# temperature_measurement.net
KiCad netlist of a schematic drawn in Altium Designer
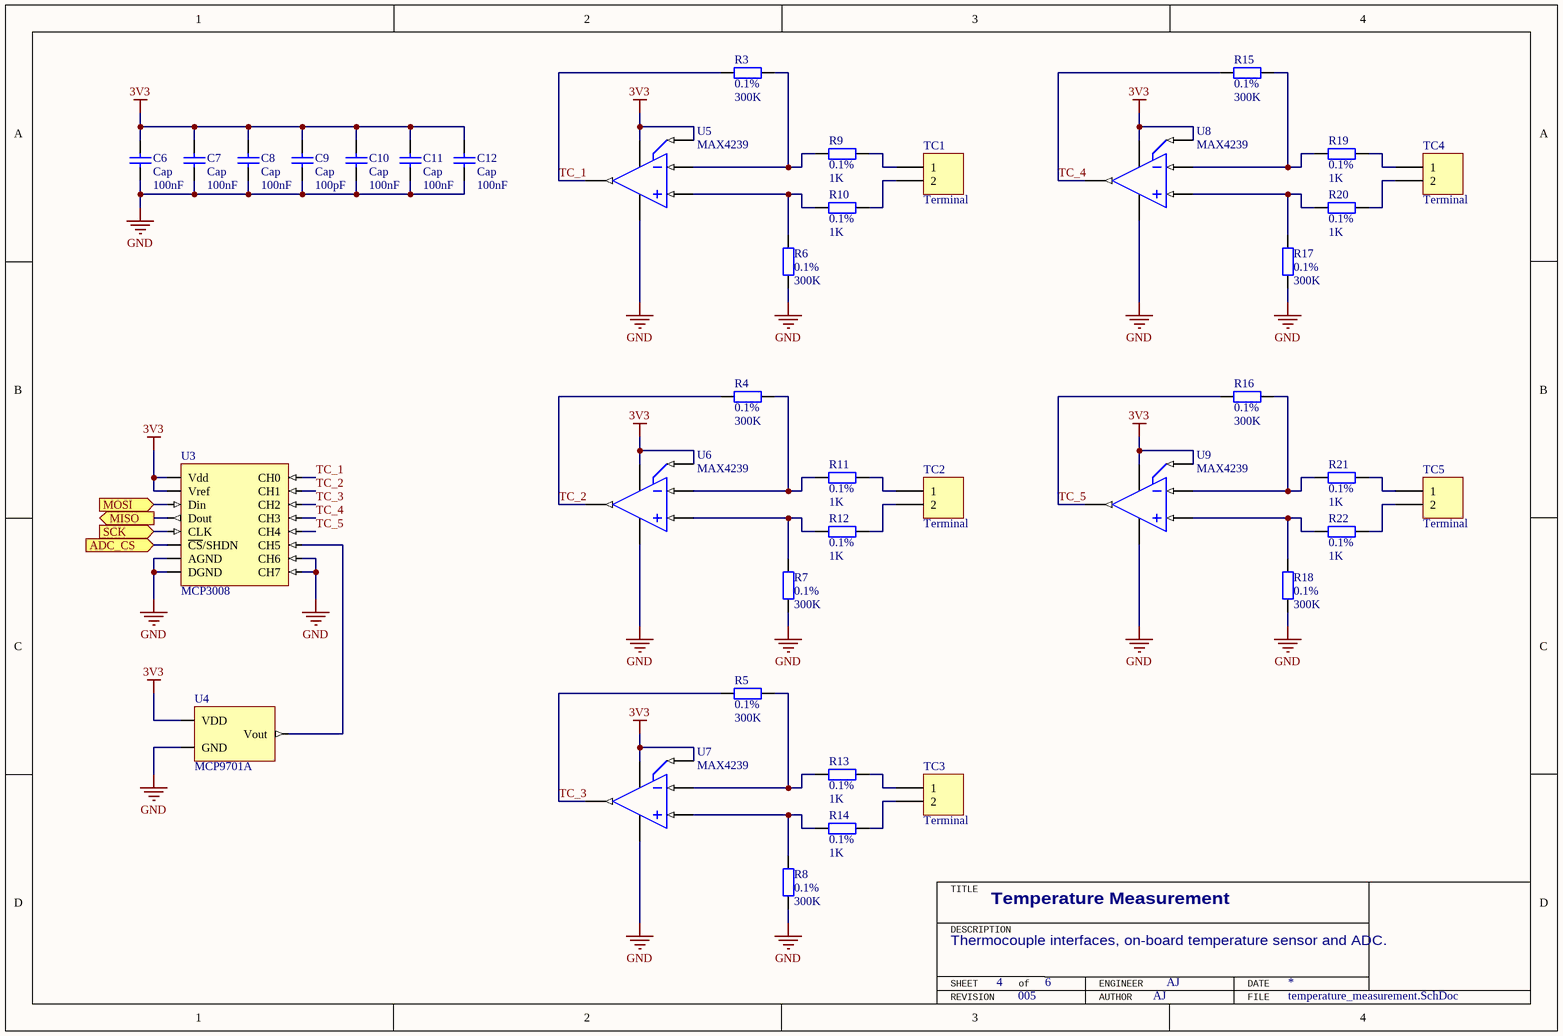
[diagram p0: temperature_measurement.SchDoc]

(export (version "E")
  (design (tool "Eeschema 10.0.6"))
  (components
    (comp (ref "C6")
      (value "Cap")
      (footprint "0603")
      (description "Capacitor")
      (fields (field (name "ALTIUM_VALUE") "100nF") (field (name "PUBLISHER") "Altium Limited"))
      (libsource (lib "Miscellaneous Devices") (part "Cap"))
    )
    (comp (ref "C7")
      (value "Cap")
      (footprint "0603")
      (description "Capacitor")
      (fields (field (name "ALTIUM_VALUE") "100nF") (field (name "PUBLISHER") "Altium Limited"))
      (libsource (lib "Miscellaneous Devices") (part "Cap"))
    )
    (comp (ref "C8")
      (value "Cap")
      (footprint "0603")
      (description "Capacitor")
      (fields (field (name "ALTIUM_VALUE") "100nF") (field (name "PUBLISHER") "Altium Limited"))
      (libsource (lib "Miscellaneous Devices") (part "Cap"))
    )
    (comp (ref "C9")
      (value "Cap")
      (footprint "0603")
      (description "Capacitor")
      (fields (field (name "ALTIUM_VALUE") "100pF") (field (name "PUBLISHER") "Altium Limited"))
      (libsource (lib "Miscellaneous Devices") (part "Cap"))
    )
    (comp (ref "C10")
      (value "Cap")
      (footprint "0603")
      (description "Capacitor")
      (fields (field (name "ALTIUM_VALUE") "100nF") (field (name "PUBLISHER") "Altium Limited"))
      (libsource (lib "Miscellaneous Devices") (part "Cap"))
    )
    (comp (ref "C11")
      (value "Cap")
      (footprint "0603")
      (description "Capacitor")
      (fields (field (name "ALTIUM_VALUE") "100nF") (field (name "PUBLISHER") "Altium Limited"))
      (libsource (lib "Miscellaneous Devices") (part "Cap"))
    )
    (comp (ref "C12")
      (value "Cap")
      (footprint "0603")
      (description "Capacitor")
      (fields (field (name "ALTIUM_VALUE") "100nF") (field (name "PUBLISHER") "Altium Limited"))
      (libsource (lib "Miscellaneous Devices") (part "Cap"))
    )
    (comp (ref "R3")
      (value "0.1%")
      (footprint "0603")
      (description "Resistor")
      (fields (field (name "ALTIUM_VALUE") "300K") (field (name "PUBLISHER") "Altium Limited"))
      (libsource (lib "") (part "Res2_2"))
    )
    (comp (ref "R4")
      (value "0.1%")
      (footprint "0603")
      (description "Resistor")
      (fields (field (name "ALTIUM_VALUE") "300K") (field (name "PUBLISHER") "Altium Limited"))
      (libsource (lib "") (part "Res2_2"))
    )
    (comp (ref "R5")
      (value "0.1%")
      (footprint "0603")
      (description "Resistor")
      (fields (field (name "ALTIUM_VALUE") "300K") (field (name "PUBLISHER") "Altium Limited"))
      (libsource (lib "") (part "Res2_2"))
    )
    (comp (ref "R6")
      (value "0.1%")
      (footprint "0603")
      (description "Resistor")
      (fields (field (name "ALTIUM_VALUE") "300K") (field (name "PUBLISHER") "Altium Limited"))
      (libsource (lib "") (part "Res2_1"))
    )
    (comp (ref "R7")
      (value "0.1%")
      (footprint "0603")
      (description "Resistor")
      (fields (field (name "ALTIUM_VALUE") "300K") (field (name "PUBLISHER") "Altium Limited"))
      (libsource (lib "") (part "Res2_1"))
    )
    (comp (ref "R8")
      (value "0.1%")
      (footprint "0603")
      (description "Resistor")
      (fields (field (name "ALTIUM_VALUE") "300K") (field (name "PUBLISHER") "Altium Limited"))
      (libsource (lib "") (part "Res2_1"))
    )
    (comp (ref "R9")
      (value "0.1%")
      (footprint "0603")
      (description "Resistor")
      (fields (field (name "ALTIUM_VALUE") "1K") (field (name "PUBLISHER") "Altium Limited"))
      (libsource (lib "Miscellaneous Devices") (part "Res2"))
    )
    (comp (ref "R10")
      (value "0.1%")
      (footprint "0603")
      (description "Resistor")
      (fields (field (name "ALTIUM_VALUE") "1K") (field (name "PUBLISHER") "Altium Limited"))
      (libsource (lib "Miscellaneous Devices") (part "Res2"))
    )
    (comp (ref "R11")
      (value "0.1%")
      (footprint "0603")
      (description "Resistor")
      (fields (field (name "ALTIUM_VALUE") "1K") (field (name "PUBLISHER") "Altium Limited"))
      (libsource (lib "Miscellaneous Devices") (part "Res2"))
    )
    (comp (ref "R12")
      (value "0.1%")
      (footprint "0603")
      (description "Resistor")
      (fields (field (name "ALTIUM_VALUE") "1K") (field (name "PUBLISHER") "Altium Limited"))
      (libsource (lib "Miscellaneous Devices") (part "Res2"))
    )
    (comp (ref "R13")
      (value "0.1%")
      (footprint "0603")
      (description "Resistor")
      (fields (field (name "ALTIUM_VALUE") "1K") (field (name "PUBLISHER") "Altium Limited"))
      (libsource (lib "Miscellaneous Devices") (part "Res2"))
    )
    (comp (ref "R14")
      (value "0.1%")
      (footprint "0603")
      (description "Resistor")
      (fields (field (name "ALTIUM_VALUE") "1K") (field (name "PUBLISHER") "Altium Limited"))
      (libsource (lib "Miscellaneous Devices") (part "Res2"))
    )
    (comp (ref "R15")
      (value "0.1%")
      (footprint "0603")
      (description "Resistor")
      (fields (field (name "ALTIUM_VALUE") "300K") (field (name "PUBLISHER") "Altium Limited"))
      (libsource (lib "") (part "Res2_2"))
    )
    (comp (ref "R16")
      (value "0.1%")
      (footprint "0603")
      (description "Resistor")
      (fields (field (name "ALTIUM_VALUE") "300K") (field (name "PUBLISHER") "Altium Limited"))
      (libsource (lib "") (part "Res2_2"))
    )
    (comp (ref "R17")
      (value "0.1%")
      (footprint "0603")
      (description "Resistor")
      (fields (field (name "ALTIUM_VALUE") "300K") (field (name "PUBLISHER") "Altium Limited"))
      (libsource (lib "") (part "Res2_1"))
    )
    (comp (ref "R18")
      (value "0.1%")
      (footprint "0603")
      (description "Resistor")
      (fields (field (name "ALTIUM_VALUE") "300K") (field (name "PUBLISHER") "Altium Limited"))
      (libsource (lib "") (part "Res2_1"))
    )
    (comp (ref "R19")
      (value "0.1%")
      (footprint "0603")
      (description "Resistor")
      (fields (field (name "ALTIUM_VALUE") "1K") (field (name "PUBLISHER") "Altium Limited"))
      (libsource (lib "Miscellaneous Devices") (part "Res2"))
    )
    (comp (ref "R20")
      (value "0.1%")
      (footprint "0603")
      (description "Resistor")
      (fields (field (name "ALTIUM_VALUE") "1K") (field (name "PUBLISHER") "Altium Limited"))
      (libsource (lib "Miscellaneous Devices") (part "Res2"))
    )
    (comp (ref "R21")
      (value "0.1%")
      (footprint "0603")
      (description "Resistor")
      (fields (field (name "ALTIUM_VALUE") "1K") (field (name "PUBLISHER") "Altium Limited"))
      (libsource (lib "Miscellaneous Devices") (part "Res2"))
    )
    (comp (ref "R22")
      (value "0.1%")
      (footprint "0603")
      (description "Resistor")
      (fields (field (name "ALTIUM_VALUE") "1K") (field (name "PUBLISHER") "Altium Limited"))
      (libsource (lib "Miscellaneous Devices") (part "Res2"))
    )
    (comp (ref "TC1")
      (value "Terminal")
      (footprint "Terminal Block")
      (description "Header, 2-Pin")
      (fields (field (name "PUBLISHER") "Altium Limited"))
      (libsource (lib "Miscellaneous Connectors") (part "Header 2"))
    )
    (comp (ref "TC2")
      (value "Terminal")
      (footprint "Terminal Block")
      (description "Header, 2-Pin")
      (fields (field (name "PUBLISHER") "Altium Limited"))
      (libsource (lib "Miscellaneous Connectors") (part "Header 2"))
    )
    (comp (ref "TC3")
      (value "Terminal")
      (footprint "Terminal Block")
      (description "Header, 2-Pin")
      (fields (field (name "PUBLISHER") "Altium Limited"))
      (libsource (lib "Miscellaneous Connectors") (part "Header 2"))
    )
    (comp (ref "TC4")
      (value "Terminal")
      (footprint "Terminal Block")
      (description "Header, 2-Pin")
      (fields (field (name "PUBLISHER") "Altium Limited"))
      (libsource (lib "Miscellaneous Connectors") (part "Header 2"))
    )
    (comp (ref "TC5")
      (value "Terminal")
      (footprint "Terminal Block")
      (description "Header, 2-Pin")
      (fields (field (name "PUBLISHER") "Altium Limited"))
      (libsource (lib "Miscellaneous Connectors") (part "Header 2"))
    )
    (comp (ref "U3")
      (value "MCP3008")
      (footprint "SO-16")
      (description "ADC 8-channel 10-bit")
      (libsource (lib "AJ") (part "MCP3008"))
    )
    (comp (ref "U4")
      (value "MCP9701A")
      (footprint "SC-70")
      (description "Low-Power Linear Active Thermistor")
      (libsource (lib "AJ") (part "MCP9701A"))
    )
    (comp (ref "U5")
      (value "MAX4239")
      (footprint "SO-8")
      (description "Ultra-Low Offset/Drift, Low-Noise,  Precision SOT23 Amplifiers")
      (libsource (lib "AJ") (part "MAX4239"))
    )
    (comp (ref "U6")
      (value "MAX4239")
      (footprint "SO-8")
      (description "Ultra-Low Offset/Drift, Low-Noise,  Precision SOT23 Amplifiers")
      (libsource (lib "AJ") (part "MAX4239"))
    )
    (comp (ref "U7")
      (value "MAX4239")
      (footprint "SO-8")
      (description "Ultra-Low Offset/Drift, Low-Noise,  Precision SOT23 Amplifiers")
      (libsource (lib "AJ") (part "MAX4239"))
    )
    (comp (ref "U8")
      (value "MAX4239")
      (footprint "SO-8")
      (description "Ultra-Low Offset/Drift, Low-Noise,  Precision SOT23 Amplifiers")
      (libsource (lib "AJ") (part "MAX4239"))
    )
    (comp (ref "U9")
      (value "MAX4239")
      (footprint "SO-8")
      (description "Ultra-Low Offset/Drift, Low-Noise,  Precision SOT23 Amplifiers")
      (libsource (lib "AJ") (part "MAX4239"))
    )
  )
  (nets
    (net (code "1") (name "/ADC_CS") (class "Default")
      (node (ref "U3") (pin "10") (pinfunction "~{CS}/SHDN_10") (pintype "passive"))
    )
    (net (code "2") (name "/MISO") (class "Default")
      (node (ref "U3") (pin "12") (pinfunction "Dout_12") (pintype "output"))
    )
    (net (code "3") (name "/MOSI") (class "Default")
      (node (ref "U3") (pin "11") (pinfunction "Din_11") (pintype "input"))
    )
    (net (code "4") (name "/SCK") (class "Default")
      (node (ref "U3") (pin "13") (pinfunction "CLK_13") (pintype "input"))
    )
    (net (code "5") (name "/TC_1") (class "Default")
      (node (ref "R3") (pin "1") (pinfunction "1_1") (pintype "passive"))
      (node (ref "U3") (pin "1") (pinfunction "CH0_1") (pintype "input"))
      (node (ref "U5") (pin "6") (pinfunction "OUT_6") (pintype "output"))
    )
    (net (code "6") (name "/TC_2") (class "Default")
      (node (ref "R4") (pin "1") (pinfunction "1_1") (pintype "passive"))
      (node (ref "U3") (pin "2") (pinfunction "CH1_2") (pintype "input"))
      (node (ref "U6") (pin "6") (pinfunction "OUT_6") (pintype "output"))
    )
    (net (code "7") (name "/TC_3") (class "Default")
      (node (ref "R5") (pin "1") (pinfunction "1_1") (pintype "passive"))
      (node (ref "U3") (pin "3") (pinfunction "CH2_3") (pintype "input"))
      (node (ref "U7") (pin "6") (pinfunction "OUT_6") (pintype "output"))
    )
    (net (code "8") (name "/TC_4") (class "Default")
      (node (ref "R15") (pin "1") (pinfunction "1_1") (pintype "passive"))
      (node (ref "U3") (pin "4") (pinfunction "CH3_4") (pintype "input"))
      (node (ref "U8") (pin "6") (pinfunction "OUT_6") (pintype "output"))
    )
    (net (code "9") (name "/TC_5") (class "Default")
      (node (ref "R16") (pin "1") (pinfunction "1_1") (pintype "passive"))
      (node (ref "U3") (pin "5") (pinfunction "CH4_5") (pintype "input"))
      (node (ref "U9") (pin "6") (pinfunction "OUT_6") (pintype "output"))
    )
    (net (code "10") (name "3V3") (class "Default")
      (node (ref "C10") (pin "2") (pinfunction "2_2") (pintype "passive"))
      (node (ref "C11") (pin "2") (pinfunction "2_2") (pintype "passive"))
      (node (ref "C12") (pin "2") (pinfunction "2_2") (pintype "passive"))
      (node (ref "C6") (pin "2") (pinfunction "2_2") (pintype "passive"))
      (node (ref "C7") (pin "2") (pinfunction "2_2") (pintype "passive"))
      (node (ref "C8") (pin "2") (pinfunction "2_2") (pintype "passive"))
      (node (ref "C9") (pin "2") (pinfunction "2_2") (pintype "passive"))
      (node (ref "U3") (pin "15") (pinfunction "Vref_15") (pintype "passive"))
      (node (ref "U3") (pin "16") (pinfunction "Vdd_16") (pintype "power_in"))
      (node (ref "U4") (pin "4") (pinfunction "VDD_4") (pintype "power_in"))
      (node (ref "U5") (pin "1") (pinfunction "~{SHDN}_1") (pintype "input"))
      (node (ref "U5") (pin "7") (pinfunction "Vcc_7") (pintype "power_in"))
      (node (ref "U6") (pin "1") (pinfunction "~{SHDN}_1") (pintype "input"))
      (node (ref "U6") (pin "7") (pinfunction "Vcc_7") (pintype "power_in"))
      (node (ref "U7") (pin "1") (pinfunction "~{SHDN}_1") (pintype "input"))
      (node (ref "U7") (pin "7") (pinfunction "Vcc_7") (pintype "power_in"))
      (node (ref "U8") (pin "1") (pinfunction "~{SHDN}_1") (pintype "input"))
      (node (ref "U8") (pin "7") (pinfunction "Vcc_7") (pintype "power_in"))
      (node (ref "U9") (pin "1") (pinfunction "~{SHDN}_1") (pintype "input"))
      (node (ref "U9") (pin "7") (pinfunction "Vcc_7") (pintype "power_in"))
    )
    (net (code "11") (name "GND") (class "Default")
      (node (ref "C10") (pin "1") (pinfunction "1_1") (pintype "passive"))
      (node (ref "C11") (pin "1") (pinfunction "1_1") (pintype "passive"))
      (node (ref "C12") (pin "1") (pinfunction "1_1") (pintype "passive"))
      (node (ref "C6") (pin "1") (pinfunction "1_1") (pintype "passive"))
      (node (ref "C7") (pin "1") (pinfunction "1_1") (pintype "passive"))
      (node (ref "C8") (pin "1") (pinfunction "1_1") (pintype "passive"))
      (node (ref "C9") (pin "1") (pinfunction "1_1") (pintype "passive"))
      (node (ref "R17") (pin "1") (pinfunction "1_1") (pintype "passive"))
      (node (ref "R18") (pin "1") (pinfunction "1_1") (pintype "passive"))
      (node (ref "R6") (pin "1") (pinfunction "1_1") (pintype "passive"))
      (node (ref "R7") (pin "1") (pinfunction "1_1") (pintype "passive"))
      (node (ref "R8") (pin "1") (pinfunction "1_1") (pintype "passive"))
      (node (ref "U3") (pin "14") (pinfunction "AGND_14") (pintype "power_in"))
      (node (ref "U3") (pin "7") (pinfunction "CH6_7") (pintype "input"))
      (node (ref "U3") (pin "8") (pinfunction "CH7_8") (pintype "input"))
      (node (ref "U3") (pin "9") (pinfunction "DGND_9") (pintype "power_in"))
      (node (ref "U4") (pin "2") (pinfunction "GND_2") (pintype "power_in"))
      (node (ref "U5") (pin "4") (pinfunction "GND_4") (pintype "power_in"))
      (node (ref "U6") (pin "4") (pinfunction "GND_4") (pintype "power_in"))
      (node (ref "U7") (pin "4") (pinfunction "GND_4") (pintype "power_in"))
      (node (ref "U8") (pin "4") (pinfunction "GND_4") (pintype "power_in"))
      (node (ref "U9") (pin "4") (pinfunction "GND_4") (pintype "power_in"))
    )
    (net (code "12") (name "Net-(R9-Pad1)") (class "Default")
      (node (ref "R9") (pin "1") (pinfunction "1_1") (pintype "passive"))
      (node (ref "TC1") (pin "1") (pinfunction "1_1") (pintype "passive"))
    )
    (net (code "13") (name "Net-(R10-Pad1)") (class "Default")
      (node (ref "R10") (pin "1") (pinfunction "1_1") (pintype "passive"))
      (node (ref "TC1") (pin "2") (pinfunction "2_2") (pintype "passive"))
    )
    (net (code "14") (name "Net-(R11-Pad1)") (class "Default")
      (node (ref "R11") (pin "1") (pinfunction "1_1") (pintype "passive"))
      (node (ref "TC2") (pin "1") (pinfunction "1_1") (pintype "passive"))
    )
    (net (code "15") (name "Net-(R12-Pad1)") (class "Default")
      (node (ref "R12") (pin "1") (pinfunction "1_1") (pintype "passive"))
      (node (ref "TC2") (pin "2") (pinfunction "2_2") (pintype "passive"))
    )
    (net (code "16") (name "Net-(R13-Pad1)") (class "Default")
      (node (ref "R13") (pin "1") (pinfunction "1_1") (pintype "passive"))
      (node (ref "TC3") (pin "1") (pinfunction "1_1") (pintype "passive"))
    )
    (net (code "17") (name "Net-(R14-Pad1)") (class "Default")
      (node (ref "R14") (pin "1") (pinfunction "1_1") (pintype "passive"))
      (node (ref "TC3") (pin "2") (pinfunction "2_2") (pintype "passive"))
    )
    (net (code "18") (name "Net-(R19-Pad1)") (class "Default")
      (node (ref "R19") (pin "1") (pinfunction "1_1") (pintype "passive"))
      (node (ref "TC4") (pin "1") (pinfunction "1_1") (pintype "passive"))
    )
    (net (code "19") (name "Net-(R20-Pad1)") (class "Default")
      (node (ref "R20") (pin "1") (pinfunction "1_1") (pintype "passive"))
      (node (ref "TC4") (pin "2") (pinfunction "2_2") (pintype "passive"))
    )
    (net (code "20") (name "Net-(R21-Pad1)") (class "Default")
      (node (ref "R21") (pin "1") (pinfunction "1_1") (pintype "passive"))
      (node (ref "TC5") (pin "1") (pinfunction "1_1") (pintype "passive"))
    )
    (net (code "21") (name "Net-(R22-Pad1)") (class "Default")
      (node (ref "R22") (pin "1") (pinfunction "1_1") (pintype "passive"))
      (node (ref "TC5") (pin "2") (pinfunction "2_2") (pintype "passive"))
    )
    (net (code "22") (name "Net-(U3-CH5)") (class "Default")
      (node (ref "U3") (pin "6") (pinfunction "CH5_6") (pintype "input"))
      (node (ref "U4") (pin "3") (pinfunction "Vout_3") (pintype "output"))
    )
    (net (code "23") (name "Net-(U5-IN+)") (class "Default")
      (node (ref "R10") (pin "2") (pinfunction "2_2") (pintype "passive"))
      (node (ref "R6") (pin "2") (pinfunction "2_2") (pintype "passive"))
      (node (ref "U5") (pin "3") (pinfunction "IN+_3") (pintype "input"))
    )
    (net (code "24") (name "Net-(U5-IN-)") (class "Default")
      (node (ref "R3") (pin "2") (pinfunction "2_2") (pintype "passive"))
      (node (ref "R9") (pin "2") (pinfunction "2_2") (pintype "passive"))
      (node (ref "U5") (pin "2") (pinfunction "IN-_2") (pintype "input"))
    )
    (net (code "25") (name "Net-(U6-IN+)") (class "Default")
      (node (ref "R12") (pin "2") (pinfunction "2_2") (pintype "passive"))
      (node (ref "R7") (pin "2") (pinfunction "2_2") (pintype "passive"))
      (node (ref "U6") (pin "3") (pinfunction "IN+_3") (pintype "input"))
    )
    (net (code "26") (name "Net-(U6-IN-)") (class "Default")
      (node (ref "R11") (pin "2") (pinfunction "2_2") (pintype "passive"))
      (node (ref "R4") (pin "2") (pinfunction "2_2") (pintype "passive"))
      (node (ref "U6") (pin "2") (pinfunction "IN-_2") (pintype "input"))
    )
    (net (code "27") (name "Net-(U7-IN+)") (class "Default")
      (node (ref "R14") (pin "2") (pinfunction "2_2") (pintype "passive"))
      (node (ref "R8") (pin "2") (pinfunction "2_2") (pintype "passive"))
      (node (ref "U7") (pin "3") (pinfunction "IN+_3") (pintype "input"))
    )
    (net (code "28") (name "Net-(U7-IN-)") (class "Default")
      (node (ref "R13") (pin "2") (pinfunction "2_2") (pintype "passive"))
      (node (ref "R5") (pin "2") (pinfunction "2_2") (pintype "passive"))
      (node (ref "U7") (pin "2") (pinfunction "IN-_2") (pintype "input"))
    )
    (net (code "29") (name "Net-(U8-IN+)") (class "Default")
      (node (ref "R17") (pin "2") (pinfunction "2_2") (pintype "passive"))
      (node (ref "R20") (pin "2") (pinfunction "2_2") (pintype "passive"))
      (node (ref "U8") (pin "3") (pinfunction "IN+_3") (pintype "input"))
    )
    (net (code "30") (name "Net-(U8-IN-)") (class "Default")
      (node (ref "R15") (pin "2") (pinfunction "2_2") (pintype "passive"))
      (node (ref "R19") (pin "2") (pinfunction "2_2") (pintype "passive"))
      (node (ref "U8") (pin "2") (pinfunction "IN-_2") (pintype "input"))
    )
    (net (code "31") (name "Net-(U9-IN+)") (class "Default")
      (node (ref "R18") (pin "2") (pinfunction "2_2") (pintype "passive"))
      (node (ref "R22") (pin "2") (pinfunction "2_2") (pintype "passive"))
      (node (ref "U9") (pin "3") (pinfunction "IN+_3") (pintype "input"))
    )
    (net (code "32") (name "Net-(U9-IN-)") (class "Default")
      (node (ref "R16") (pin "2") (pinfunction "2_2") (pintype "passive"))
      (node (ref "R21") (pin "2") (pinfunction "2_2") (pintype "passive"))
      (node (ref "U9") (pin "2") (pinfunction "IN-_2") (pintype "input"))
    )
  )
)
